# EduRobController.net
KiCad netlist of a schematic drawn in EAGLE
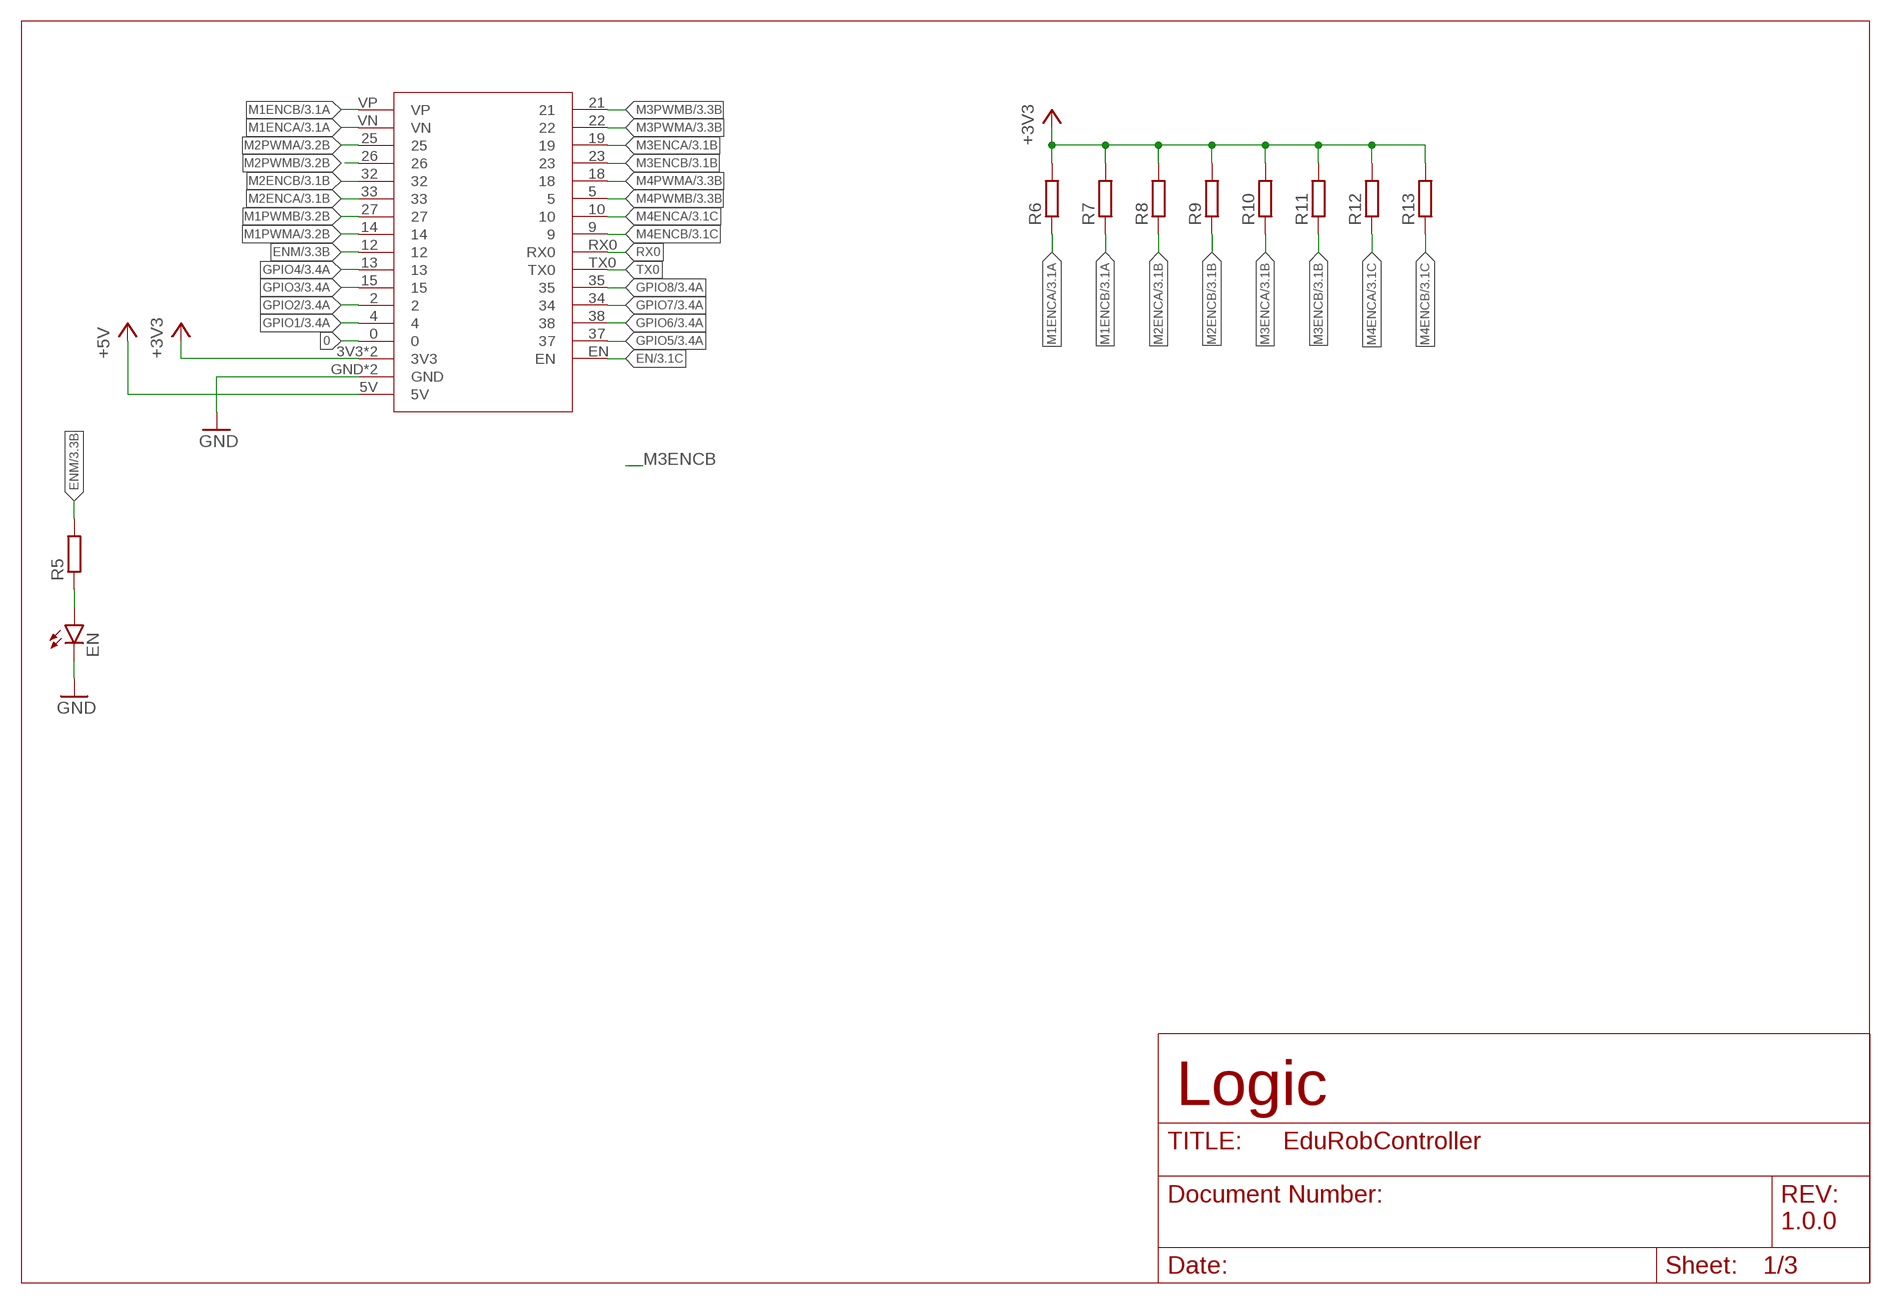
[diagram p0: schematic, sheet 1]
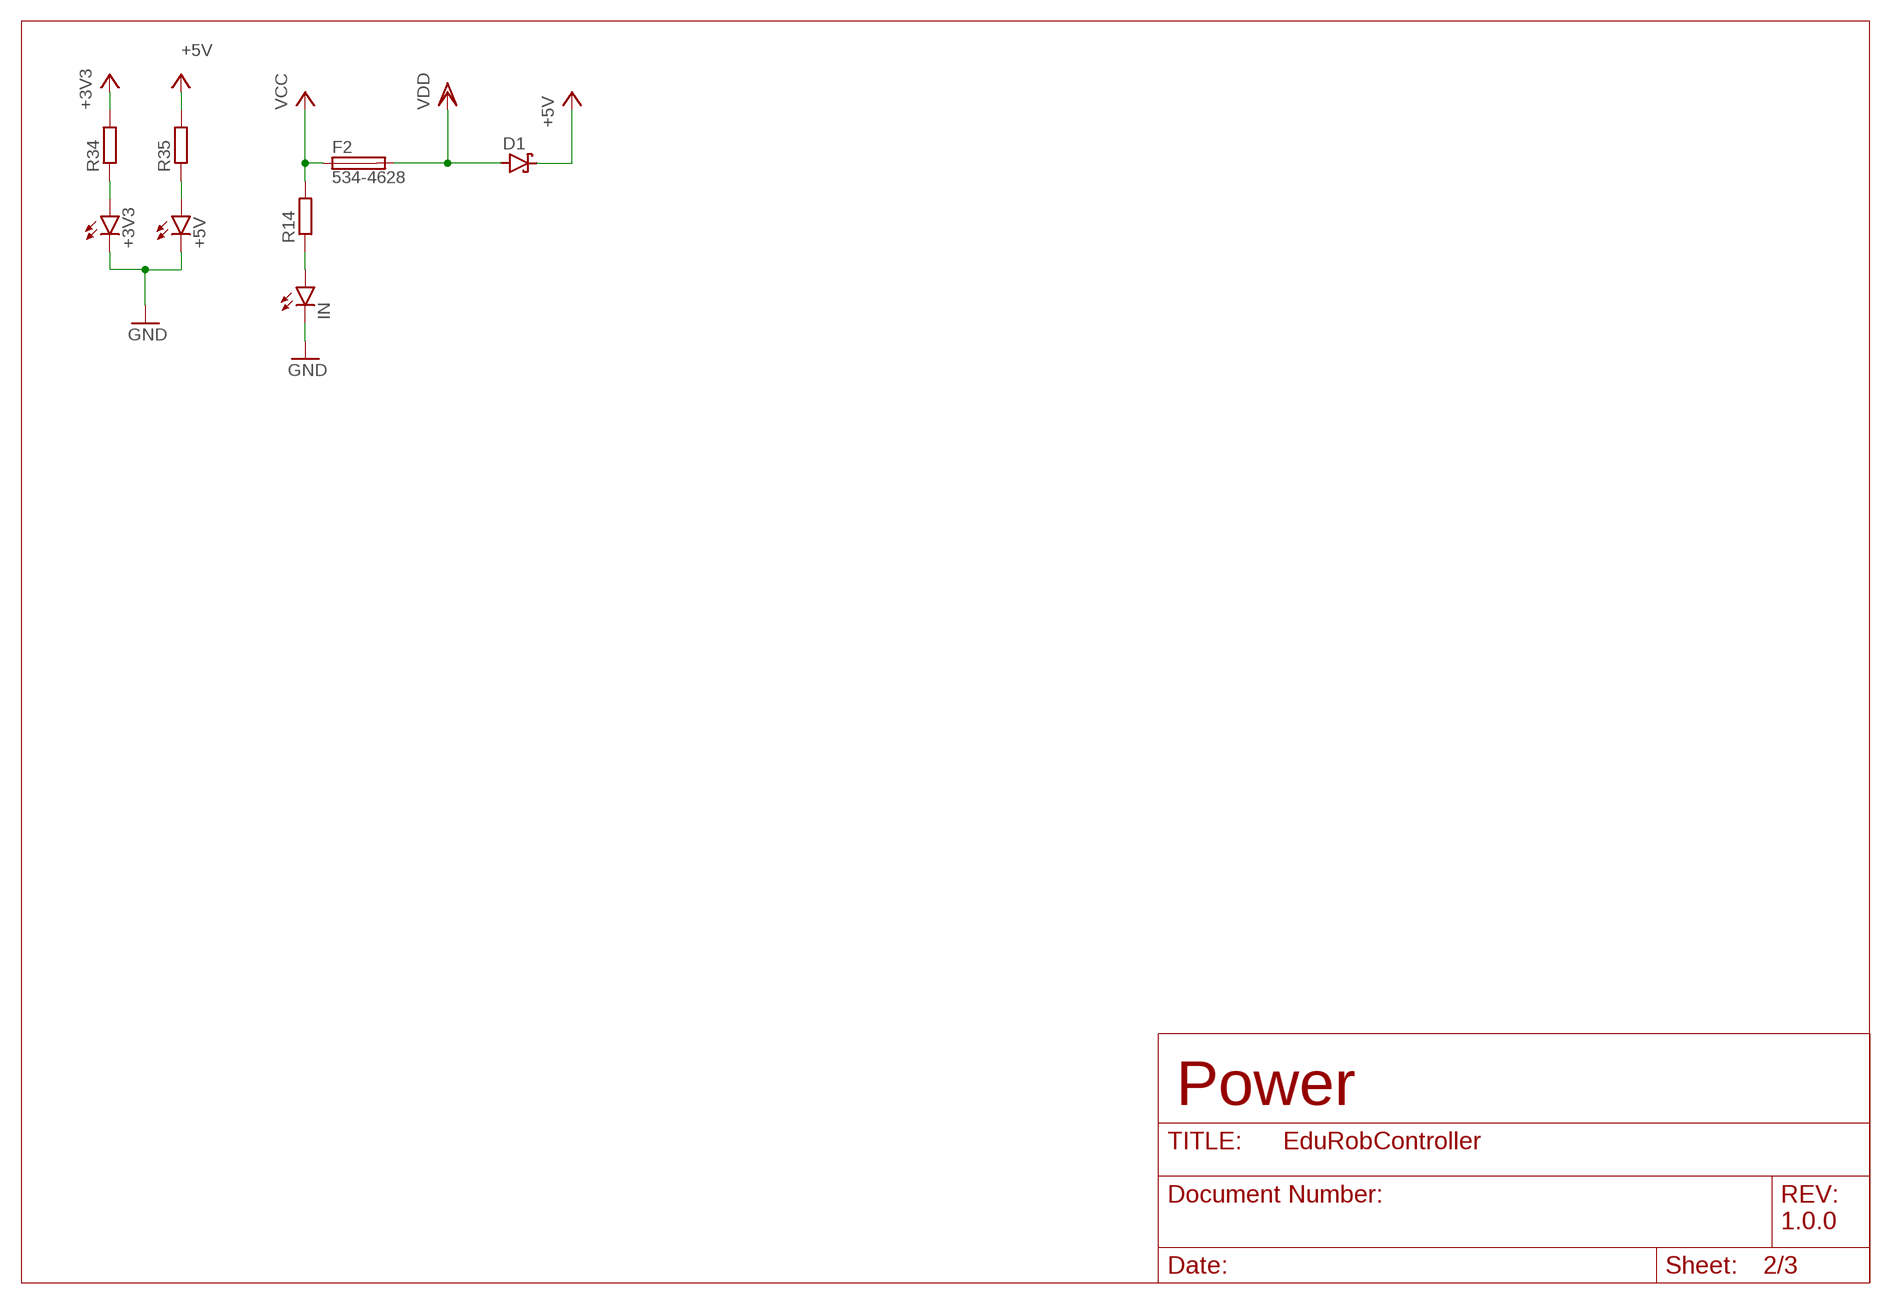
[diagram p1: schematic, sheet 2]
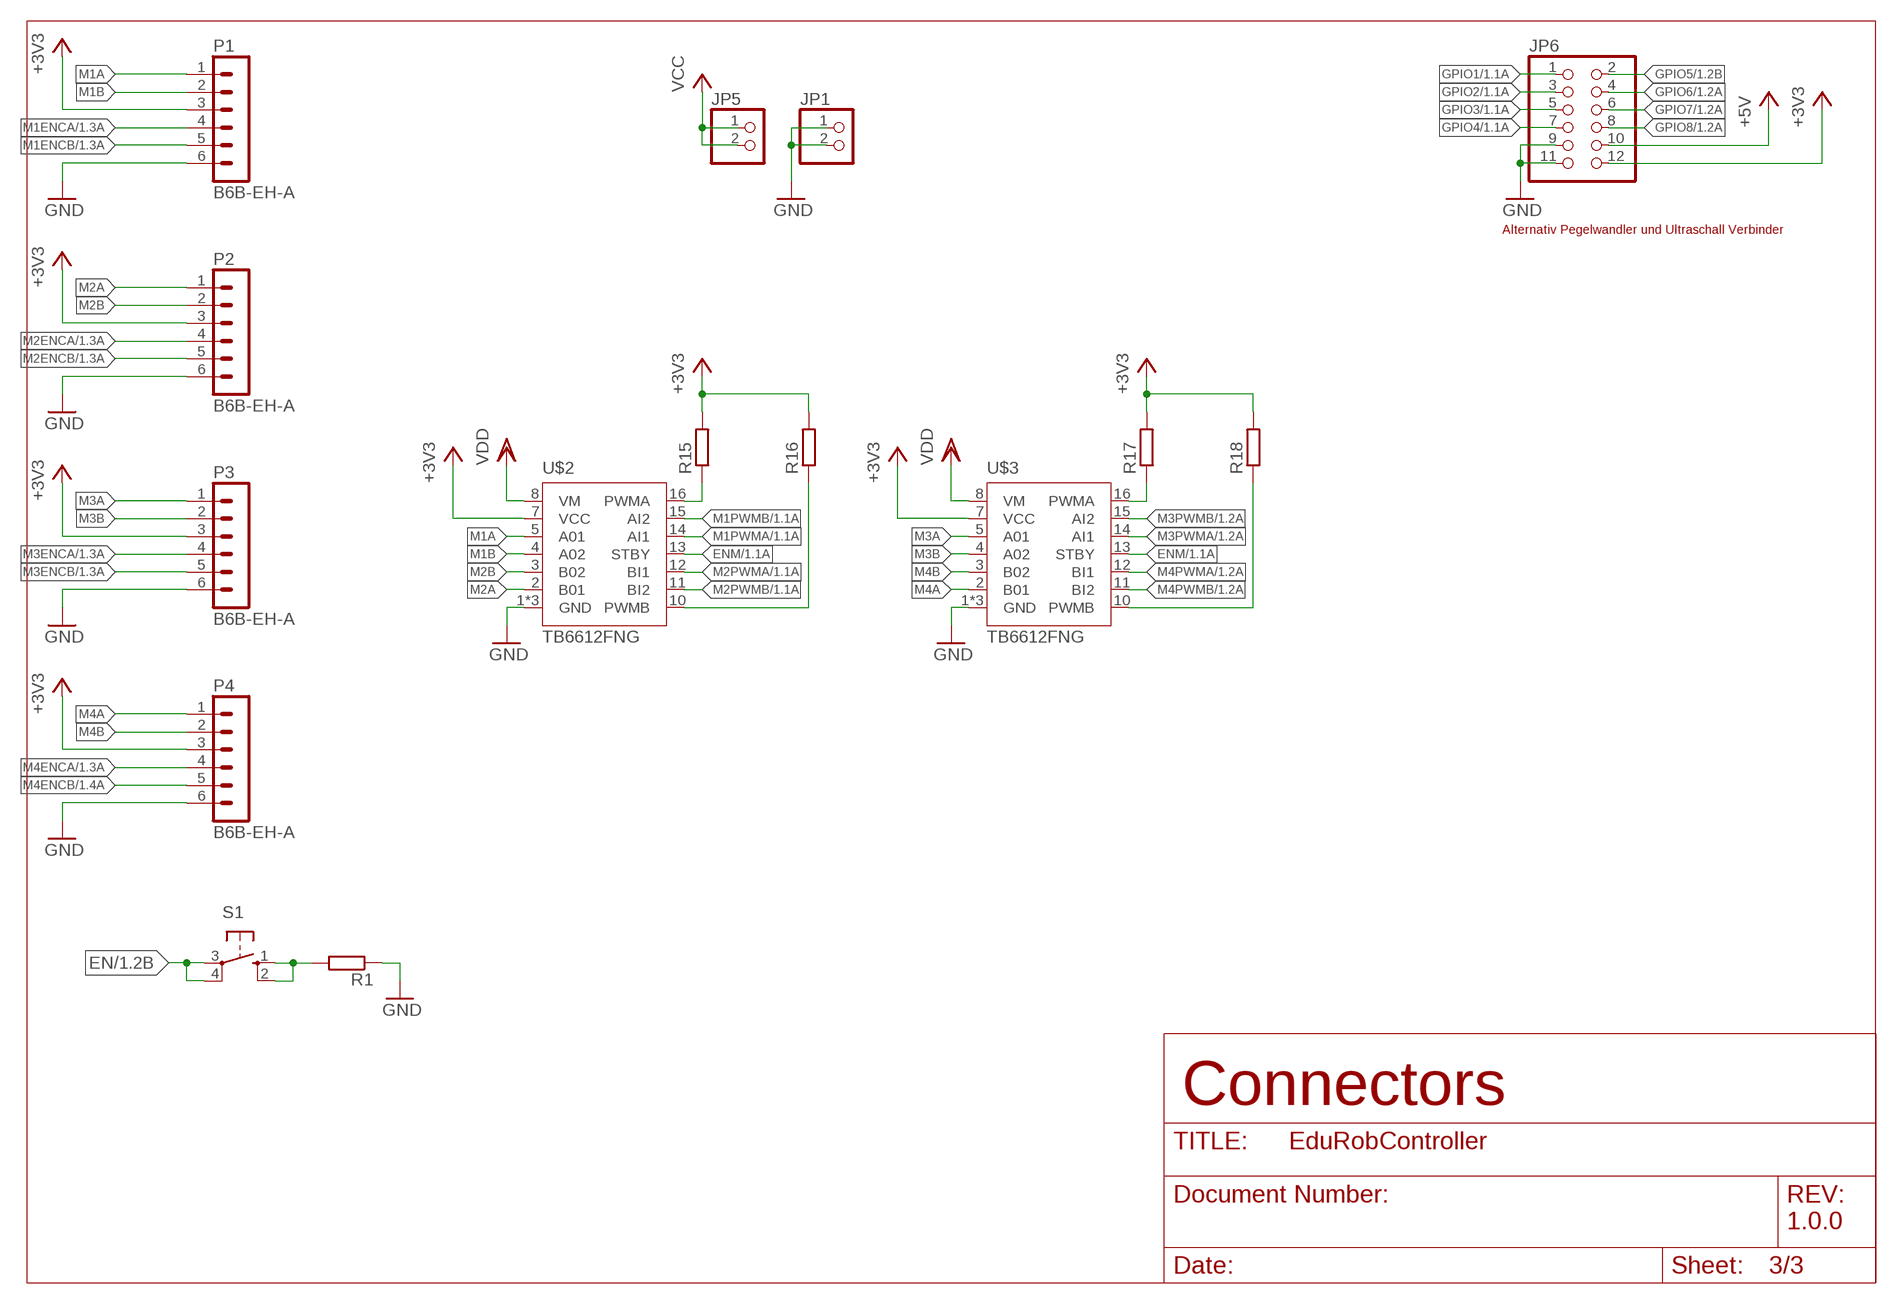
[diagram p2: schematic, sheet 3]

(export (version "E")
  (design (tool "Eeschema 10.0.6"))
  (components
    (comp (ref "EN")
      (value "LEDCHIP-LED0805")
      (footprint "eagle-import:CHIP-LED0805")
      (libsource (lib "eagle-import") (part "LEDCHIP-LED0805"))
    )
    (comp (ref "R5")
      (value "R-EU_R0805")
      (footprint "eagle-import:R0805")
      (libsource (lib "eagle-import") (part "R-EU_R0805"))
    )
    (comp (ref "R6")
      (value "R-EU_R0603")
      (footprint "eagle-import:R0603")
      (libsource (lib "eagle-import") (part "R-EU_R0603"))
    )
    (comp (ref "R7")
      (value "R-EU_R0603")
      (footprint "eagle-import:R0603")
      (libsource (lib "eagle-import") (part "R-EU_R0603"))
    )
    (comp (ref "R8")
      (value "R-EU_R0603")
      (footprint "eagle-import:R0603")
      (libsource (lib "eagle-import") (part "R-EU_R0603"))
    )
    (comp (ref "R9")
      (value "R-EU_R0603")
      (footprint "eagle-import:R0603")
      (libsource (lib "eagle-import") (part "R-EU_R0603"))
    )
    (comp (ref "R10")
      (value "R-EU_R0603")
      (footprint "eagle-import:R0603")
      (libsource (lib "eagle-import") (part "R-EU_R0603"))
    )
    (comp (ref "R11")
      (value "R-EU_R0603")
      (footprint "eagle-import:R0603")
      (libsource (lib "eagle-import") (part "R-EU_R0603"))
    )
    (comp (ref "R12")
      (value "R-EU_R0603")
      (footprint "eagle-import:R0603")
      (libsource (lib "eagle-import") (part "R-EU_R0603"))
    )
    (comp (ref "R13")
      (value "R-EU_R0603")
      (footprint "eagle-import:R0603")
      (libsource (lib "eagle-import") (part "R-EU_R0603"))
    )
    (comp (ref "U$1")
      (value "ESP32")
      (footprint "eagle-import:ESP32")
      (libsource (lib "eagle-import") (part "ESP32"))
    )
    (comp (ref "+3V3")
      (value "LEDCHIP-LED0805")
      (footprint "eagle-import:CHIP-LED0805")
      (libsource (lib "eagle-import") (part "LEDCHIP-LED0805"))
    )
    (comp (ref "+5V")
      (value "LEDCHIP-LED0805")
      (footprint "eagle-import:CHIP-LED0805")
      (libsource (lib "eagle-import") (part "LEDCHIP-LED0805"))
    )
    (comp (ref "D1")
      (value "SCHOTTKY-DIODESMD")
      (footprint "eagle-import:SMB")
      (libsource (lib "eagle-import") (part "SCHOTTKY-DIODESMD"))
    )
    (comp (ref "F2")
      (value "534-4628")
      (footprint "eagle-import:SH22,5")
      (fields (field (name "MF") "SCHURTER") (field (name "MPN") "0031.8201"))
      (libsource (lib "eagle-import") (part "SH22,5"))
    )
    (comp (ref "IN")
      (value "LEDCHIP-LED0805")
      (footprint "eagle-import:CHIP-LED0805")
      (libsource (lib "eagle-import") (part "LEDCHIP-LED0805"))
    )
    (comp (ref "R14")
      (value "R-EU_R0805")
      (footprint "eagle-import:R0805")
      (libsource (lib "eagle-import") (part "R-EU_R0805"))
    )
    (comp (ref "R34")
      (value "R-EU_R0805")
      (footprint "eagle-import:R0805")
      (libsource (lib "eagle-import") (part "R-EU_R0805"))
    )
    (comp (ref "R35")
      (value "R-EU_R0805")
      (footprint "eagle-import:R0805")
      (libsource (lib "eagle-import") (part "R-EU_R0805"))
    )
    (comp (ref "JP1")
      (value "PINHD-1X2")
      (footprint "eagle-import:1X02")
      (libsource (lib "eagle-import") (part "PINHD-1X2"))
    )
    (comp (ref "JP5")
      (value "PINHD-1X2")
      (footprint "eagle-import:1X02")
      (libsource (lib "eagle-import") (part "PINHD-1X2"))
    )
    (comp (ref "JP6")
      (value "PINHD-2X6")
      (footprint "eagle-import:2X06")
      (libsource (lib "eagle-import") (part "PINHD-2X6"))
    )
    (comp (ref "P1")
      (value "B6B-EH-A")
      (footprint "eagle-import:B6B-EH-A")
      (libsource (lib "eagle-import") (part "B6B-EH-A"))
    )
    (comp (ref "P2")
      (value "B6B-EH-A")
      (footprint "eagle-import:B6B-EH-A")
      (libsource (lib "eagle-import") (part "B6B-EH-A"))
    )
    (comp (ref "P3")
      (value "B6B-EH-A")
      (footprint "eagle-import:B6B-EH-A")
      (libsource (lib "eagle-import") (part "B6B-EH-A"))
    )
    (comp (ref "P4")
      (value "B6B-EH-A")
      (footprint "eagle-import:B6B-EH-A")
      (libsource (lib "eagle-import") (part "B6B-EH-A"))
    )
    (comp (ref "R1")
      (value "R-EU_R0603")
      (footprint "eagle-import:R0603")
      (libsource (lib "eagle-import") (part "R-EU_R0603"))
    )
    (comp (ref "R15")
      (value "R-EU_R0603")
      (footprint "eagle-import:R0603")
      (libsource (lib "eagle-import") (part "R-EU_R0603"))
    )
    (comp (ref "R16")
      (value "R-EU_R0603")
      (footprint "eagle-import:R0603")
      (libsource (lib "eagle-import") (part "R-EU_R0603"))
    )
    (comp (ref "R17")
      (value "R-EU_R0603")
      (footprint "eagle-import:R0603")
      (libsource (lib "eagle-import") (part "R-EU_R0603"))
    )
    (comp (ref "R18")
      (value "R-EU_R0603")
      (footprint "eagle-import:R0603")
      (libsource (lib "eagle-import") (part "R-EU_R0603"))
    )
    (comp (ref "S1")
      (value "10-XX")
      (footprint "eagle-import:B3F-10XX")
      (fields (field (name "MPN") "B3F-1000"))
      (libsource (lib "eagle-import") (part "10-XX"))
    )
    (comp (ref "U$2")
      (value "TB6612FNG")
      (footprint "eagle-import:2X08")
      (libsource (lib "eagle-import") (part "TB6612FNG"))
    )
    (comp (ref "U$3")
      (value "TB6612FNG")
      (footprint "eagle-import:2X08")
      (libsource (lib "eagle-import") (part "TB6612FNG"))
    )
  )
  (nets
    (net (code "1") (name "+3V3") (class "Default")
      (node (ref "JP6") (pin "12") (pinfunction "12_12") (pintype "passive"))
      (node (ref "P1") (pin "3") (pinfunction "3_3") (pintype "passive"))
      (node (ref "P2") (pin "3") (pinfunction "3_3") (pintype "passive"))
      (node (ref "P3") (pin "3") (pinfunction "3_3") (pintype "passive"))
      (node (ref "P4") (pin "3") (pinfunction "3_3") (pintype "passive"))
      (node (ref "R10") (pin "2") (pinfunction "2_2") (pintype "passive"))
      (node (ref "R11") (pin "2") (pinfunction "2_2") (pintype "passive"))
      (node (ref "R12") (pin "2") (pinfunction "2_2") (pintype "passive"))
      (node (ref "R13") (pin "2") (pinfunction "2_2") (pintype "passive"))
      (node (ref "R15") (pin "2") (pinfunction "2_2") (pintype "passive"))
      (node (ref "R16") (pin "2") (pinfunction "2_2") (pintype "passive"))
      (node (ref "R17") (pin "2") (pinfunction "2_2") (pintype "passive"))
      (node (ref "R18") (pin "2") (pinfunction "2_2") (pintype "passive"))
      (node (ref "R34") (pin "2") (pinfunction "2_2") (pintype "passive"))
      (node (ref "R6") (pin "2") (pinfunction "2_2") (pintype "passive"))
      (node (ref "R7") (pin "2") (pinfunction "2_2") (pintype "passive"))
      (node (ref "R8") (pin "2") (pinfunction "2_2") (pintype "passive"))
      (node (ref "R9") (pin "2") (pinfunction "2_2") (pintype "passive"))
      (node (ref "U$1") (pin "3V3") (pinfunction "3V3_3V3") (pintype "bidirectional"))
      (node (ref "U$1") (pin "3V3.") (pinfunction "3V3_3V3.") (pintype "bidirectional"))
      (node (ref "U$2") (pin "7") (pinfunction "VCC_7") (pintype "bidirectional"))
      (node (ref "U$3") (pin "7") (pinfunction "VCC_7") (pintype "bidirectional"))
    )
    (net (code "2") (name "+5V") (class "Default")
      (node (ref "D1") (pin "C") (pinfunction "C_C") (pintype "passive"))
      (node (ref "JP6") (pin "10") (pinfunction "10_10") (pintype "passive"))
      (node (ref "R35") (pin "2") (pinfunction "2_2") (pintype "passive"))
      (node (ref "U$1") (pin "5V") (pinfunction "5V_5V") (pintype "bidirectional"))
    )
    (net (code "3") (name "0") (class "Default")
      (node (ref "U$1") (pin "0") (pinfunction "0_0") (pintype "bidirectional"))
    )
    (net (code "4") (name "EN") (class "Default")
      (node (ref "S1") (pin "3") (pinfunction "P_3") (pintype "passive"))
      (node (ref "S1") (pin "4") (pinfunction "P1_4") (pintype "passive"))
      (node (ref "U$1") (pin "EN") (pinfunction "EN_EN") (pintype "bidirectional"))
    )
    (net (code "5") (name "ENM") (class "Default")
      (node (ref "R5") (pin "2") (pinfunction "2_2") (pintype "passive"))
      (node (ref "U$1") (pin "12") (pinfunction "12_12") (pintype "bidirectional"))
      (node (ref "U$2") (pin "13") (pinfunction "STBY_13") (pintype "bidirectional"))
      (node (ref "U$3") (pin "13") (pinfunction "STBY_13") (pintype "bidirectional"))
    )
    (net (code "6") (name "GND") (class "Default")
      (node (ref "+3V3") (pin "C") (pinfunction "C_C") (pintype "passive"))
      (node (ref "+5V") (pin "C") (pinfunction "C_C") (pintype "passive"))
      (node (ref "EN") (pin "C") (pinfunction "C_C") (pintype "passive"))
      (node (ref "IN") (pin "C") (pinfunction "C_C") (pintype "passive"))
      (node (ref "JP1") (pin "1") (pinfunction "1_1") (pintype "passive"))
      (node (ref "JP1") (pin "2") (pinfunction "2_2") (pintype "passive"))
      (node (ref "JP6") (pin "11") (pinfunction "11_11") (pintype "passive"))
      (node (ref "JP6") (pin "9") (pinfunction "9_9") (pintype "passive"))
      (node (ref "P1") (pin "6") (pinfunction "6_6") (pintype "passive"))
      (node (ref "P2") (pin "6") (pinfunction "6_6") (pintype "passive"))
      (node (ref "P3") (pin "6") (pinfunction "6_6") (pintype "passive"))
      (node (ref "P4") (pin "6") (pinfunction "6_6") (pintype "passive"))
      (node (ref "R1") (pin "1") (pinfunction "1_1") (pintype "passive"))
      (node (ref "U$1") (pin "GND") (pinfunction "GND_GND") (pintype "bidirectional"))
      (node (ref "U$1") (pin "GND.") (pinfunction "GND_GND.") (pintype "bidirectional"))
      (node (ref "U$2") (pin "1") (pinfunction "GND_1") (pintype "bidirectional"))
      (node (ref "U$2") (pin "6") (pinfunction "GND_6") (pintype "bidirectional"))
      (node (ref "U$2") (pin "9") (pinfunction "GND_9") (pintype "bidirectional"))
      (node (ref "U$3") (pin "1") (pinfunction "GND_1") (pintype "bidirectional"))
      (node (ref "U$3") (pin "6") (pinfunction "GND_6") (pintype "bidirectional"))
      (node (ref "U$3") (pin "9") (pinfunction "GND_9") (pintype "bidirectional"))
    )
    (net (code "7") (name "GPIO1") (class "Default")
      (node (ref "JP6") (pin "1") (pinfunction "1_1") (pintype "passive"))
      (node (ref "U$1") (pin "4") (pinfunction "4_4") (pintype "bidirectional"))
    )
    (net (code "8") (name "GPIO2") (class "Default")
      (node (ref "JP6") (pin "3") (pinfunction "3_3") (pintype "passive"))
      (node (ref "U$1") (pin "2") (pinfunction "2_2") (pintype "bidirectional"))
    )
    (net (code "9") (name "GPIO3") (class "Default")
      (node (ref "JP6") (pin "5") (pinfunction "5_5") (pintype "passive"))
      (node (ref "U$1") (pin "15") (pinfunction "15_15") (pintype "bidirectional"))
    )
    (net (code "10") (name "GPIO4") (class "Default")
      (node (ref "JP6") (pin "7") (pinfunction "7_7") (pintype "passive"))
      (node (ref "U$1") (pin "13") (pinfunction "13_13") (pintype "bidirectional"))
    )
    (net (code "11") (name "GPIO5") (class "Default")
      (node (ref "JP6") (pin "2") (pinfunction "2_2") (pintype "passive"))
      (node (ref "U$1") (pin "37") (pinfunction "37_37") (pintype "bidirectional"))
    )
    (net (code "12") (name "GPIO6") (class "Default")
      (node (ref "JP6") (pin "4") (pinfunction "4_4") (pintype "passive"))
      (node (ref "U$1") (pin "38") (pinfunction "38_38") (pintype "bidirectional"))
    )
    (net (code "13") (name "GPIO7") (class "Default")
      (node (ref "JP6") (pin "6") (pinfunction "6_6") (pintype "passive"))
      (node (ref "U$1") (pin "34") (pinfunction "34_34") (pintype "bidirectional"))
    )
    (net (code "14") (name "GPIO8") (class "Default")
      (node (ref "JP6") (pin "8") (pinfunction "8_8") (pintype "passive"))
      (node (ref "U$1") (pin "35") (pinfunction "35_35") (pintype "bidirectional"))
    )
    (net (code "15") (name "M1A") (class "Default")
      (node (ref "P1") (pin "1") (pinfunction "1_1") (pintype "passive"))
      (node (ref "U$2") (pin "5") (pinfunction "A01_5") (pintype "bidirectional"))
    )
    (net (code "16") (name "M1B") (class "Default")
      (node (ref "P1") (pin "2") (pinfunction "2_2") (pintype "passive"))
      (node (ref "U$2") (pin "4") (pinfunction "A02_4") (pintype "bidirectional"))
    )
    (net (code "17") (name "M1ENCA") (class "Default")
      (node (ref "P1") (pin "4") (pinfunction "4_4") (pintype "passive"))
      (node (ref "R6") (pin "1") (pinfunction "1_1") (pintype "passive"))
      (node (ref "U$1") (pin "VN") (pinfunction "VN_VN") (pintype "bidirectional"))
    )
    (net (code "18") (name "M1ENCB") (class "Default")
      (node (ref "P1") (pin "5") (pinfunction "5_5") (pintype "passive"))
      (node (ref "R7") (pin "1") (pinfunction "1_1") (pintype "passive"))
      (node (ref "U$1") (pin "VP") (pinfunction "VP_VP") (pintype "bidirectional"))
    )
    (net (code "19") (name "M1PWMA") (class "Default")
      (node (ref "U$1") (pin "14") (pinfunction "14_14") (pintype "bidirectional"))
      (node (ref "U$2") (pin "14") (pinfunction "AI1_14") (pintype "bidirectional"))
    )
    (net (code "20") (name "M1PWMB") (class "Default")
      (node (ref "U$1") (pin "27") (pinfunction "27_27") (pintype "bidirectional"))
      (node (ref "U$2") (pin "15") (pinfunction "AI2_15") (pintype "bidirectional"))
    )
    (net (code "21") (name "M2A") (class "Default")
      (node (ref "P2") (pin "1") (pinfunction "1_1") (pintype "passive"))
      (node (ref "U$2") (pin "2") (pinfunction "B01_2") (pintype "bidirectional"))
    )
    (net (code "22") (name "M2B") (class "Default")
      (node (ref "P2") (pin "2") (pinfunction "2_2") (pintype "passive"))
      (node (ref "U$2") (pin "3") (pinfunction "B02_3") (pintype "bidirectional"))
    )
    (net (code "23") (name "M2ENCA") (class "Default")
      (node (ref "P2") (pin "4") (pinfunction "4_4") (pintype "passive"))
      (node (ref "R8") (pin "1") (pinfunction "1_1") (pintype "passive"))
      (node (ref "U$1") (pin "33") (pinfunction "33_33") (pintype "bidirectional"))
    )
    (net (code "24") (name "M2ENCB") (class "Default")
      (node (ref "P2") (pin "5") (pinfunction "5_5") (pintype "passive"))
      (node (ref "R9") (pin "1") (pinfunction "1_1") (pintype "passive"))
      (node (ref "U$1") (pin "32") (pinfunction "32_32") (pintype "bidirectional"))
    )
    (net (code "25") (name "M2PWMA") (class "Default")
      (node (ref "U$1") (pin "25") (pinfunction "25_25") (pintype "bidirectional"))
      (node (ref "U$2") (pin "12") (pinfunction "BI1_12") (pintype "bidirectional"))
    )
    (net (code "26") (name "M2PWMB") (class "Default")
      (node (ref "U$1") (pin "26") (pinfunction "26_26") (pintype "bidirectional"))
      (node (ref "U$2") (pin "11") (pinfunction "BI2_11") (pintype "bidirectional"))
    )
    (net (code "27") (name "M3A") (class "Default")
      (node (ref "P3") (pin "1") (pinfunction "1_1") (pintype "passive"))
      (node (ref "U$3") (pin "5") (pinfunction "A01_5") (pintype "bidirectional"))
    )
    (net (code "28") (name "M3B") (class "Default")
      (node (ref "P3") (pin "2") (pinfunction "2_2") (pintype "passive"))
      (node (ref "U$3") (pin "4") (pinfunction "A02_4") (pintype "bidirectional"))
    )
    (net (code "29") (name "M3ENCA") (class "Default")
      (node (ref "P3") (pin "4") (pinfunction "4_4") (pintype "passive"))
      (node (ref "R10") (pin "1") (pinfunction "1_1") (pintype "passive"))
      (node (ref "U$1") (pin "19") (pinfunction "19_19") (pintype "bidirectional"))
    )
    (net (code "30") (name "M3ENCB") (class "Default")
      (node (ref "P3") (pin "5") (pinfunction "5_5") (pintype "passive"))
      (node (ref "R11") (pin "1") (pinfunction "1_1") (pintype "passive"))
      (node (ref "U$1") (pin "23") (pinfunction "23_23") (pintype "bidirectional"))
    )
    (net (code "31") (name "M3PWMA") (class "Default")
      (node (ref "U$1") (pin "22") (pinfunction "22_22") (pintype "bidirectional"))
      (node (ref "U$3") (pin "14") (pinfunction "AI1_14") (pintype "bidirectional"))
    )
    (net (code "32") (name "M3PWMB") (class "Default")
      (node (ref "U$1") (pin "21") (pinfunction "21_21") (pintype "bidirectional"))
      (node (ref "U$3") (pin "15") (pinfunction "AI2_15") (pintype "bidirectional"))
    )
    (net (code "33") (name "M4A") (class "Default")
      (node (ref "P4") (pin "1") (pinfunction "1_1") (pintype "passive"))
      (node (ref "U$3") (pin "2") (pinfunction "B01_2") (pintype "bidirectional"))
    )
    (net (code "34") (name "M4B") (class "Default")
      (node (ref "P4") (pin "2") (pinfunction "2_2") (pintype "passive"))
      (node (ref "U$3") (pin "3") (pinfunction "B02_3") (pintype "bidirectional"))
    )
    (net (code "35") (name "M4ENCA") (class "Default")
      (node (ref "P4") (pin "4") (pinfunction "4_4") (pintype "passive"))
      (node (ref "R12") (pin "1") (pinfunction "1_1") (pintype "passive"))
      (node (ref "U$1") (pin "10") (pinfunction "10_10") (pintype "bidirectional"))
    )
    (net (code "36") (name "M4ENCB") (class "Default")
      (node (ref "P4") (pin "5") (pinfunction "5_5") (pintype "passive"))
      (node (ref "R13") (pin "1") (pinfunction "1_1") (pintype "passive"))
      (node (ref "U$1") (pin "9") (pinfunction "9_9") (pintype "bidirectional"))
    )
    (net (code "37") (name "M4PWMA") (class "Default")
      (node (ref "U$1") (pin "18") (pinfunction "18_18") (pintype "bidirectional"))
      (node (ref "U$3") (pin "12") (pinfunction "BI1_12") (pintype "bidirectional"))
    )
    (net (code "38") (name "M4PWMB") (class "Default")
      (node (ref "U$1") (pin "5") (pinfunction "5_5") (pintype "bidirectional"))
      (node (ref "U$3") (pin "11") (pinfunction "BI2_11") (pintype "bidirectional"))
    )
    (net (code "39") (name "Net-(+3V3-PadA)") (class "Default")
      (node (ref "+3V3") (pin "A") (pinfunction "A_A") (pintype "passive"))
      (node (ref "R34") (pin "1") (pinfunction "1_1") (pintype "passive"))
    )
    (net (code "40") (name "Net-(+5V-PadA)") (class "Default")
      (node (ref "+5V") (pin "A") (pinfunction "A_A") (pintype "passive"))
      (node (ref "R35") (pin "1") (pinfunction "1_1") (pintype "passive"))
    )
    (net (code "41") (name "Net-(EN-PadA)") (class "Default")
      (node (ref "EN") (pin "A") (pinfunction "A_A") (pintype "passive"))
      (node (ref "R5") (pin "1") (pinfunction "1_1") (pintype "passive"))
    )
    (net (code "42") (name "Net-(IN-PadA)") (class "Default")
      (node (ref "IN") (pin "A") (pinfunction "A_A") (pintype "passive"))
      (node (ref "R14") (pin "1") (pinfunction "1_1") (pintype "passive"))
    )
    (net (code "43") (name "Net-(S1-S)") (class "Default")
      (node (ref "R1") (pin "2") (pinfunction "2_2") (pintype "passive"))
      (node (ref "S1") (pin "1") (pinfunction "S_1") (pintype "passive"))
      (node (ref "S1") (pin "2") (pinfunction "S1_2") (pintype "passive"))
    )
    (net (code "44") (name "Net-(U$2-PWMA)") (class "Default")
      (node (ref "R15") (pin "1") (pinfunction "1_1") (pintype "passive"))
      (node (ref "U$2") (pin "16") (pinfunction "PWMA_16") (pintype "bidirectional"))
    )
    (net (code "45") (name "Net-(U$2-PWMB)") (class "Default")
      (node (ref "R16") (pin "1") (pinfunction "1_1") (pintype "passive"))
      (node (ref "U$2") (pin "10") (pinfunction "PWMB_10") (pintype "bidirectional"))
    )
    (net (code "46") (name "Net-(U$3-PWMA)") (class "Default")
      (node (ref "R17") (pin "1") (pinfunction "1_1") (pintype "passive"))
      (node (ref "U$3") (pin "16") (pinfunction "PWMA_16") (pintype "bidirectional"))
    )
    (net (code "47") (name "Net-(U$3-PWMB)") (class "Default")
      (node (ref "R18") (pin "1") (pinfunction "1_1") (pintype "passive"))
      (node (ref "U$3") (pin "10") (pinfunction "PWMB_10") (pintype "bidirectional"))
    )
    (net (code "48") (name "RX0") (class "Default")
      (node (ref "U$1") (pin "RX0") (pinfunction "RX0_RX0") (pintype "bidirectional"))
    )
    (net (code "49") (name "TX0") (class "Default")
      (node (ref "U$1") (pin "TX0") (pinfunction "TX0_TX0") (pintype "bidirectional"))
    )
    (net (code "50") (name "VCC") (class "Default")
      (node (ref "F2") (pin "1") (pinfunction "1_1") (pintype "passive"))
      (node (ref "JP5") (pin "1") (pinfunction "1_1") (pintype "passive"))
      (node (ref "JP5") (pin "2") (pinfunction "2_2") (pintype "passive"))
      (node (ref "R14") (pin "2") (pinfunction "2_2") (pintype "passive"))
    )
    (net (code "51") (name "VDD") (class "Default")
      (node (ref "D1") (pin "A") (pinfunction "A_A") (pintype "passive"))
      (node (ref "F2") (pin "2") (pinfunction "2_2") (pintype "passive"))
      (node (ref "U$2") (pin "8") (pinfunction "VM_8") (pintype "bidirectional"))
      (node (ref "U$3") (pin "8") (pinfunction "VM_8") (pintype "bidirectional"))
    )
  )
)
